# BMS_Adapter_Segment.net
KiCad netlist of a schematic drawn in EAGLE
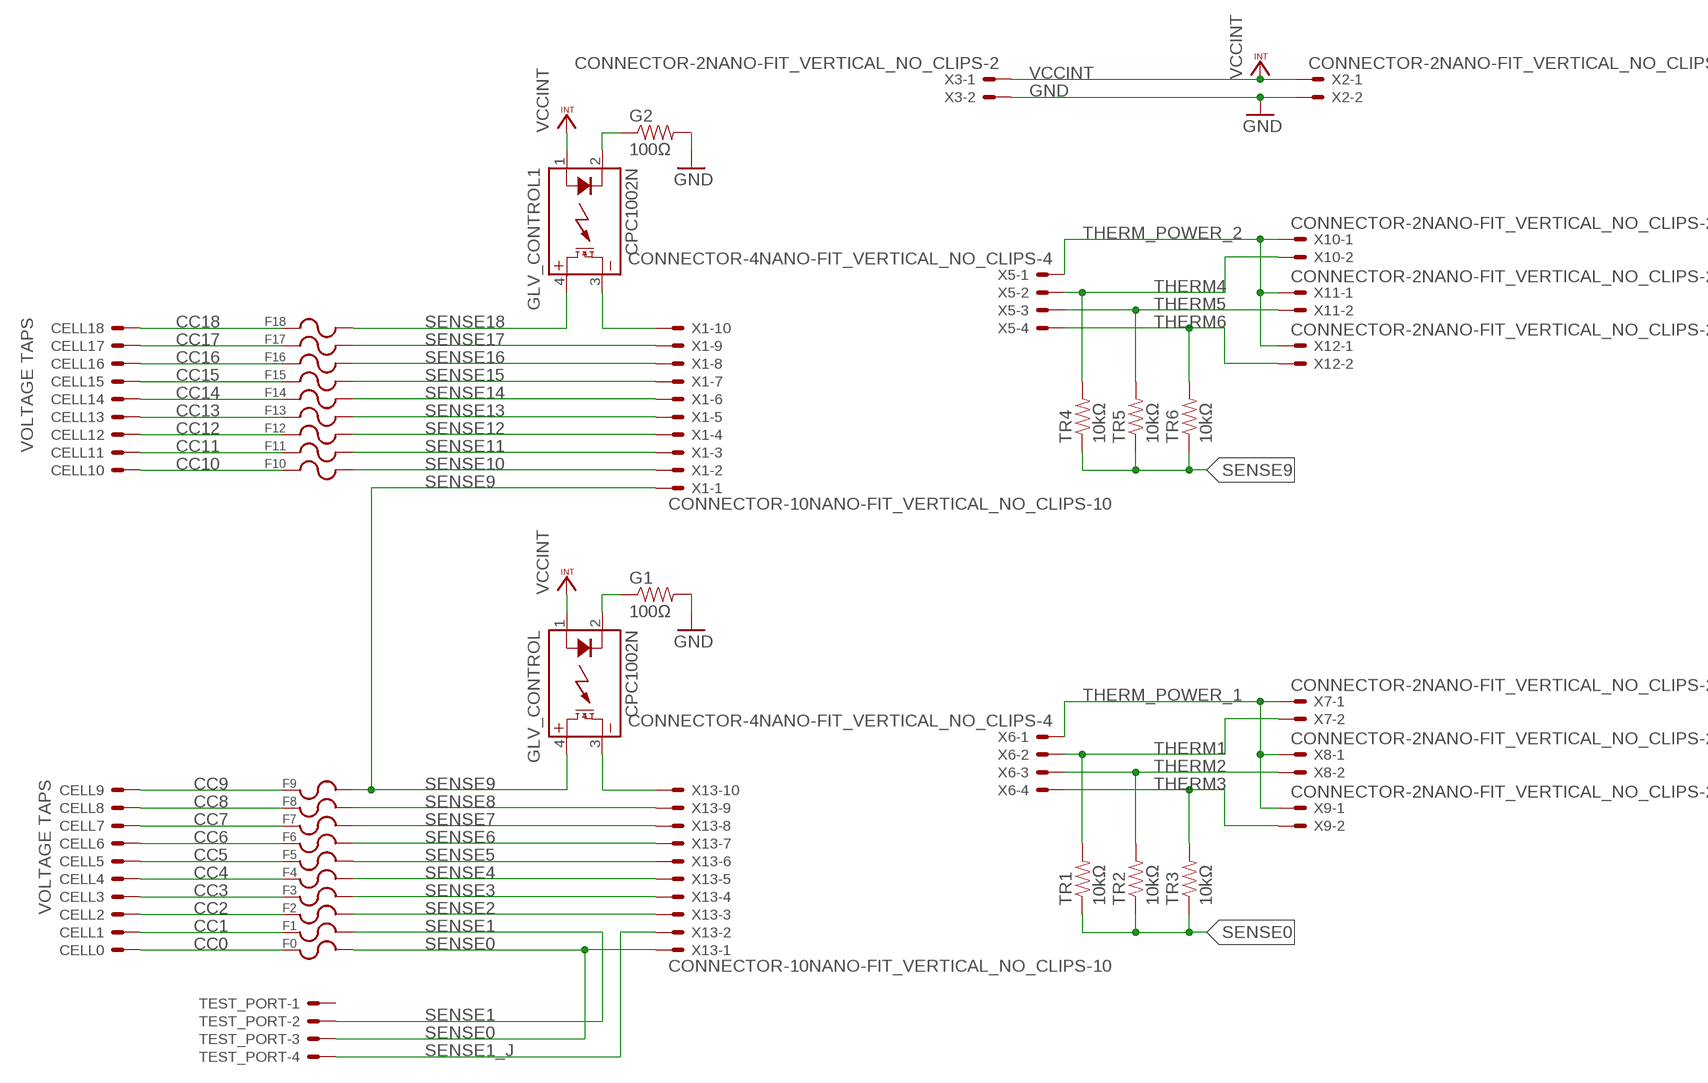
[diagram p0: schematic, sheet 1]

(export (version "E")
  (design (tool "Eeschema 10.0.6"))
  (components
    (comp (ref "CELL0")
      (value "BATTERY_SPRING_KEYSTONE5222")
      (footprint "eagle-import:KEYSTONE5222")
      (libsource (lib "eagle-import") (part "BATTERY_SPRING_KEYSTONE5222"))
    )
    (comp (ref "CELL1")
      (value "BATTERY_SPRING_KEYSTONE5222")
      (footprint "eagle-import:KEYSTONE5222")
      (libsource (lib "eagle-import") (part "BATTERY_SPRING_KEYSTONE5222"))
    )
    (comp (ref "CELL2")
      (value "BATTERY_SPRING_KEYSTONE5222")
      (footprint "eagle-import:KEYSTONE5222")
      (libsource (lib "eagle-import") (part "BATTERY_SPRING_KEYSTONE5222"))
    )
    (comp (ref "CELL3")
      (value "BATTERY_SPRING_KEYSTONE5222")
      (footprint "eagle-import:KEYSTONE5222")
      (libsource (lib "eagle-import") (part "BATTERY_SPRING_KEYSTONE5222"))
    )
    (comp (ref "CELL4")
      (value "BATTERY_SPRING_KEYSTONE5222")
      (footprint "eagle-import:KEYSTONE5222")
      (libsource (lib "eagle-import") (part "BATTERY_SPRING_KEYSTONE5222"))
    )
    (comp (ref "CELL5")
      (value "BATTERY_SPRING_KEYSTONE5222")
      (footprint "eagle-import:KEYSTONE5222")
      (libsource (lib "eagle-import") (part "BATTERY_SPRING_KEYSTONE5222"))
    )
    (comp (ref "CELL6")
      (value "BATTERY_SPRING_KEYSTONE5222")
      (footprint "eagle-import:KEYSTONE5222")
      (libsource (lib "eagle-import") (part "BATTERY_SPRING_KEYSTONE5222"))
    )
    (comp (ref "CELL7")
      (value "BATTERY_SPRING_KEYSTONE5222")
      (footprint "eagle-import:KEYSTONE5222")
      (libsource (lib "eagle-import") (part "BATTERY_SPRING_KEYSTONE5222"))
    )
    (comp (ref "CELL8")
      (value "BATTERY_SPRING_KEYSTONE5222")
      (footprint "eagle-import:KEYSTONE5222")
      (libsource (lib "eagle-import") (part "BATTERY_SPRING_KEYSTONE5222"))
    )
    (comp (ref "CELL9")
      (value "BATTERY_SPRING_KEYSTONE5222")
      (footprint "eagle-import:KEYSTONE5222")
      (libsource (lib "eagle-import") (part "BATTERY_SPRING_KEYSTONE5222"))
    )
    (comp (ref "CELL10")
      (value "BATTERY_SPRING_KEYSTONE5222")
      (footprint "eagle-import:KEYSTONE5222")
      (libsource (lib "eagle-import") (part "BATTERY_SPRING_KEYSTONE5222"))
    )
    (comp (ref "CELL11")
      (value "BATTERY_SPRING_KEYSTONE5222")
      (footprint "eagle-import:KEYSTONE5222")
      (libsource (lib "eagle-import") (part "BATTERY_SPRING_KEYSTONE5222"))
    )
    (comp (ref "CELL12")
      (value "BATTERY_SPRING_KEYSTONE5222")
      (footprint "eagle-import:KEYSTONE5222")
      (libsource (lib "eagle-import") (part "BATTERY_SPRING_KEYSTONE5222"))
    )
    (comp (ref "CELL13")
      (value "BATTERY_SPRING_KEYSTONE5222")
      (footprint "eagle-import:KEYSTONE5222")
      (libsource (lib "eagle-import") (part "BATTERY_SPRING_KEYSTONE5222"))
    )
    (comp (ref "CELL14")
      (value "BATTERY_SPRING_KEYSTONE5222")
      (footprint "eagle-import:KEYSTONE5222")
      (libsource (lib "eagle-import") (part "BATTERY_SPRING_KEYSTONE5222"))
    )
    (comp (ref "CELL15")
      (value "BATTERY_SPRING_KEYSTONE5222")
      (footprint "eagle-import:KEYSTONE5222")
      (libsource (lib "eagle-import") (part "BATTERY_SPRING_KEYSTONE5222"))
    )
    (comp (ref "CELL16")
      (value "BATTERY_SPRING_KEYSTONE5222")
      (footprint "eagle-import:KEYSTONE5222")
      (libsource (lib "eagle-import") (part "BATTERY_SPRING_KEYSTONE5222"))
    )
    (comp (ref "CELL17")
      (value "BATTERY_SPRING_KEYSTONE5222")
      (footprint "eagle-import:KEYSTONE5222")
      (libsource (lib "eagle-import") (part "BATTERY_SPRING_KEYSTONE5222"))
    )
    (comp (ref "CELL18")
      (value "BATTERY_SPRING_KEYSTONE5222")
      (footprint "eagle-import:KEYSTONE5222")
      (libsource (lib "eagle-import") (part "BATTERY_SPRING_KEYSTONE5222"))
    )
    (comp (ref "F0")
      (value "0751.0110_FUSE_CLIP")
      (footprint "eagle-import:0751.0110")
      (libsource (lib "eagle-import") (part "0751.0110_FUSE_CLIP"))
    )
    (comp (ref "F1")
      (value "0751.0110_FUSE_CLIP")
      (footprint "eagle-import:0751.0110")
      (libsource (lib "eagle-import") (part "0751.0110_FUSE_CLIP"))
    )
    (comp (ref "F2")
      (value "0751.0110_FUSE_CLIP")
      (footprint "eagle-import:0751.0110")
      (libsource (lib "eagle-import") (part "0751.0110_FUSE_CLIP"))
    )
    (comp (ref "F3")
      (value "0751.0110_FUSE_CLIP")
      (footprint "eagle-import:0751.0110")
      (libsource (lib "eagle-import") (part "0751.0110_FUSE_CLIP"))
    )
    (comp (ref "F4")
      (value "0751.0110_FUSE_CLIP")
      (footprint "eagle-import:0751.0110")
      (libsource (lib "eagle-import") (part "0751.0110_FUSE_CLIP"))
    )
    (comp (ref "F5")
      (value "0751.0110_FUSE_CLIP")
      (footprint "eagle-import:0751.0110")
      (libsource (lib "eagle-import") (part "0751.0110_FUSE_CLIP"))
    )
    (comp (ref "F6")
      (value "0751.0110_FUSE_CLIP")
      (footprint "eagle-import:0751.0110")
      (libsource (lib "eagle-import") (part "0751.0110_FUSE_CLIP"))
    )
    (comp (ref "F7")
      (value "0751.0110_FUSE_CLIP")
      (footprint "eagle-import:0751.0110")
      (libsource (lib "eagle-import") (part "0751.0110_FUSE_CLIP"))
    )
    (comp (ref "F8")
      (value "0751.0110_FUSE_CLIP")
      (footprint "eagle-import:0751.0110")
      (libsource (lib "eagle-import") (part "0751.0110_FUSE_CLIP"))
    )
    (comp (ref "F9")
      (value "0751.0110_FUSE_CLIP")
      (footprint "eagle-import:0751.0110")
      (libsource (lib "eagle-import") (part "0751.0110_FUSE_CLIP"))
    )
    (comp (ref "F10")
      (value "0751.0110_FUSE_CLIP")
      (footprint "eagle-import:0751.0110")
      (libsource (lib "eagle-import") (part "0751.0110_FUSE_CLIP"))
    )
    (comp (ref "F11")
      (value "0751.0110_FUSE_CLIP")
      (footprint "eagle-import:0751.0110")
      (libsource (lib "eagle-import") (part "0751.0110_FUSE_CLIP"))
    )
    (comp (ref "F12")
      (value "0751.0110_FUSE_CLIP")
      (footprint "eagle-import:0751.0110")
      (libsource (lib "eagle-import") (part "0751.0110_FUSE_CLIP"))
    )
    (comp (ref "F13")
      (value "0751.0110_FUSE_CLIP")
      (footprint "eagle-import:0751.0110")
      (libsource (lib "eagle-import") (part "0751.0110_FUSE_CLIP"))
    )
    (comp (ref "F14")
      (value "0751.0110_FUSE_CLIP")
      (footprint "eagle-import:0751.0110")
      (libsource (lib "eagle-import") (part "0751.0110_FUSE_CLIP"))
    )
    (comp (ref "F15")
      (value "0751.0110_FUSE_CLIP")
      (footprint "eagle-import:0751.0110")
      (libsource (lib "eagle-import") (part "0751.0110_FUSE_CLIP"))
    )
    (comp (ref "F16")
      (value "0751.0110_FUSE_CLIP")
      (footprint "eagle-import:0751.0110")
      (libsource (lib "eagle-import") (part "0751.0110_FUSE_CLIP"))
    )
    (comp (ref "F17")
      (value "0751.0110_FUSE_CLIP")
      (footprint "eagle-import:0751.0110")
      (libsource (lib "eagle-import") (part "0751.0110_FUSE_CLIP"))
    )
    (comp (ref "F18")
      (value "0751.0110_FUSE_CLIP")
      (footprint "eagle-import:0751.0110")
      (libsource (lib "eagle-import") (part "0751.0110_FUSE_CLIP"))
    )
    (comp (ref "G1")
      (value "100Ω")
      (footprint "eagle-import:0805")
      (libsource (lib "eagle-import") (part "RESISTOR0805-RES"))
    )
    (comp (ref "G2")
      (value "100Ω")
      (footprint "eagle-import:0805")
      (libsource (lib "eagle-import") (part "RESISTOR0805-RES"))
    )
    (comp (ref "GLV_CONTROL")
      (value "CPC1002N")
      (footprint "eagle-import:SOP04")
      (libsource (lib "eagle-import") (part "CPC1002N"))
    )
    (comp (ref "GLV_CONTROL1")
      (value "CPC1002N")
      (footprint "eagle-import:SOP04")
      (libsource (lib "eagle-import") (part "CPC1002N"))
    )
    (comp (ref "TEST_PORT")
      (value "MINIFIT_5566-4")
      (footprint "eagle-import:MINIFIT_5566-4")
      (libsource (lib "eagle-import") (part "MINIFIT_5566-4"))
    )
    (comp (ref "TR1")
      (value "10kΩ")
      (footprint "eagle-import:0805")
      (libsource (lib "eagle-import") (part "RESISTOR0805-RES"))
    )
    (comp (ref "TR2")
      (value "10kΩ")
      (footprint "eagle-import:0805")
      (libsource (lib "eagle-import") (part "RESISTOR0805-RES"))
    )
    (comp (ref "TR3")
      (value "10kΩ")
      (footprint "eagle-import:0805")
      (libsource (lib "eagle-import") (part "RESISTOR0805-RES"))
    )
    (comp (ref "TR4")
      (value "10kΩ")
      (footprint "eagle-import:0805")
      (libsource (lib "eagle-import") (part "RESISTOR0805-RES"))
    )
    (comp (ref "TR5")
      (value "10kΩ")
      (footprint "eagle-import:0805")
      (libsource (lib "eagle-import") (part "RESISTOR0805-RES"))
    )
    (comp (ref "TR6")
      (value "10kΩ")
      (footprint "eagle-import:0805")
      (libsource (lib "eagle-import") (part "RESISTOR0805-RES"))
    )
    (comp (ref "X1")
      (value "CONNECTOR-10NANO-FIT_VERTICAL_NO_CLIPS-10")
      (footprint "eagle-import:NANO-FIT_VERTICAL_NO_CLIPS-10")
      (libsource (lib "eagle-import") (part "CONNECTOR-10NANO-FIT_VERTICAL_NO_CLIPS-10"))
    )
    (comp (ref "X2")
      (value "CONNECTOR-2NANO-FIT_VERTICAL_NO_CLIPS-2")
      (footprint "eagle-import:NANO-FIT_VERTICAL_NO_CLIPS-2")
      (libsource (lib "eagle-import") (part "CONNECTOR-2NANO-FIT_VERTICAL_NO_CLIPS-2"))
    )
    (comp (ref "X3")
      (value "CONNECTOR-2NANO-FIT_VERTICAL_NO_CLIPS-2")
      (footprint "eagle-import:NANO-FIT_VERTICAL_NO_CLIPS-2")
      (libsource (lib "eagle-import") (part "CONNECTOR-2NANO-FIT_VERTICAL_NO_CLIPS-2"))
    )
    (comp (ref "X5")
      (value "CONNECTOR-4NANO-FIT_VERTICAL_NO_CLIPS-4")
      (footprint "eagle-import:NANO-FIT_VERTICAL_NO_CLIPS-4")
      (libsource (lib "eagle-import") (part "CONNECTOR-4NANO-FIT_VERTICAL_NO_CLIPS-4"))
    )
    (comp (ref "X6")
      (value "CONNECTOR-4NANO-FIT_VERTICAL_NO_CLIPS-4")
      (footprint "eagle-import:NANO-FIT_VERTICAL_NO_CLIPS-4")
      (libsource (lib "eagle-import") (part "CONNECTOR-4NANO-FIT_VERTICAL_NO_CLIPS-4"))
    )
    (comp (ref "X7")
      (value "CONNECTOR-2NANO-FIT_VERTICAL_NO_CLIPS-2")
      (footprint "eagle-import:NANO-FIT_VERTICAL_NO_CLIPS-2")
      (libsource (lib "eagle-import") (part "CONNECTOR-2NANO-FIT_VERTICAL_NO_CLIPS-2"))
    )
    (comp (ref "X8")
      (value "CONNECTOR-2NANO-FIT_VERTICAL_NO_CLIPS-2")
      (footprint "eagle-import:NANO-FIT_VERTICAL_NO_CLIPS-2")
      (libsource (lib "eagle-import") (part "CONNECTOR-2NANO-FIT_VERTICAL_NO_CLIPS-2"))
    )
    (comp (ref "X9")
      (value "CONNECTOR-2NANO-FIT_VERTICAL_NO_CLIPS-2")
      (footprint "eagle-import:NANO-FIT_VERTICAL_NO_CLIPS-2")
      (libsource (lib "eagle-import") (part "CONNECTOR-2NANO-FIT_VERTICAL_NO_CLIPS-2"))
    )
    (comp (ref "X10")
      (value "CONNECTOR-2NANO-FIT_VERTICAL_NO_CLIPS-2")
      (footprint "eagle-import:NANO-FIT_VERTICAL_NO_CLIPS-2")
      (libsource (lib "eagle-import") (part "CONNECTOR-2NANO-FIT_VERTICAL_NO_CLIPS-2"))
    )
    (comp (ref "X11")
      (value "CONNECTOR-2NANO-FIT_VERTICAL_NO_CLIPS-2")
      (footprint "eagle-import:NANO-FIT_VERTICAL_NO_CLIPS-2")
      (libsource (lib "eagle-import") (part "CONNECTOR-2NANO-FIT_VERTICAL_NO_CLIPS-2"))
    )
    (comp (ref "X12")
      (value "CONNECTOR-2NANO-FIT_VERTICAL_NO_CLIPS-2")
      (footprint "eagle-import:NANO-FIT_VERTICAL_NO_CLIPS-2")
      (libsource (lib "eagle-import") (part "CONNECTOR-2NANO-FIT_VERTICAL_NO_CLIPS-2"))
    )
    (comp (ref "X13")
      (value "CONNECTOR-10NANO-FIT_VERTICAL_NO_CLIPS-10")
      (footprint "eagle-import:NANO-FIT_VERTICAL_NO_CLIPS-10")
      (libsource (lib "eagle-import") (part "CONNECTOR-10NANO-FIT_VERTICAL_NO_CLIPS-10"))
    )
  )
  (nets
    (net (code "1") (name "/CC0") (class "Default")
      (node (ref "CELL0") (pin "P$1") (pinfunction "S_P$1") (pintype "passive"))
      (node (ref "F0") (pin "L1") (pinfunction "1_L1") (pintype "bidirectional"))
      (node (ref "F0") (pin "L2") (pinfunction "1_L2") (pintype "bidirectional"))
    )
    (net (code "2") (name "/CC1") (class "Default")
      (node (ref "CELL1") (pin "P$1") (pinfunction "S_P$1") (pintype "passive"))
      (node (ref "F1") (pin "L1") (pinfunction "1_L1") (pintype "bidirectional"))
      (node (ref "F1") (pin "L2") (pinfunction "1_L2") (pintype "bidirectional"))
    )
    (net (code "3") (name "/CC2") (class "Default")
      (node (ref "CELL2") (pin "P$1") (pinfunction "S_P$1") (pintype "passive"))
      (node (ref "F2") (pin "L1") (pinfunction "1_L1") (pintype "bidirectional"))
      (node (ref "F2") (pin "L2") (pinfunction "1_L2") (pintype "bidirectional"))
    )
    (net (code "4") (name "/CC3") (class "Default")
      (node (ref "CELL3") (pin "P$1") (pinfunction "S_P$1") (pintype "passive"))
      (node (ref "F3") (pin "L1") (pinfunction "1_L1") (pintype "bidirectional"))
      (node (ref "F3") (pin "L2") (pinfunction "1_L2") (pintype "bidirectional"))
    )
    (net (code "5") (name "/CC4") (class "Default")
      (node (ref "CELL4") (pin "P$1") (pinfunction "S_P$1") (pintype "passive"))
      (node (ref "F4") (pin "L1") (pinfunction "1_L1") (pintype "bidirectional"))
      (node (ref "F4") (pin "L2") (pinfunction "1_L2") (pintype "bidirectional"))
    )
    (net (code "6") (name "/CC5") (class "Default")
      (node (ref "CELL5") (pin "P$1") (pinfunction "S_P$1") (pintype "passive"))
      (node (ref "F5") (pin "L1") (pinfunction "1_L1") (pintype "bidirectional"))
      (node (ref "F5") (pin "L2") (pinfunction "1_L2") (pintype "bidirectional"))
    )
    (net (code "7") (name "/CC6") (class "Default")
      (node (ref "CELL6") (pin "P$1") (pinfunction "S_P$1") (pintype "passive"))
      (node (ref "F6") (pin "L1") (pinfunction "1_L1") (pintype "bidirectional"))
      (node (ref "F6") (pin "L2") (pinfunction "1_L2") (pintype "bidirectional"))
    )
    (net (code "8") (name "/CC7") (class "Default")
      (node (ref "CELL7") (pin "P$1") (pinfunction "S_P$1") (pintype "passive"))
      (node (ref "F7") (pin "L1") (pinfunction "1_L1") (pintype "bidirectional"))
      (node (ref "F7") (pin "L2") (pinfunction "1_L2") (pintype "bidirectional"))
    )
    (net (code "9") (name "/CC8") (class "Default")
      (node (ref "CELL8") (pin "P$1") (pinfunction "S_P$1") (pintype "passive"))
      (node (ref "F8") (pin "L1") (pinfunction "1_L1") (pintype "bidirectional"))
      (node (ref "F8") (pin "L2") (pinfunction "1_L2") (pintype "bidirectional"))
    )
    (net (code "10") (name "/CC9") (class "Default")
      (node (ref "CELL9") (pin "P$1") (pinfunction "S_P$1") (pintype "passive"))
      (node (ref "F9") (pin "L1") (pinfunction "1_L1") (pintype "bidirectional"))
      (node (ref "F9") (pin "L2") (pinfunction "1_L2") (pintype "bidirectional"))
    )
    (net (code "11") (name "/CC10") (class "Default")
      (node (ref "CELL10") (pin "P$1") (pinfunction "S_P$1") (pintype "passive"))
      (node (ref "F10") (pin "L1") (pinfunction "1_L1") (pintype "bidirectional"))
      (node (ref "F10") (pin "L2") (pinfunction "1_L2") (pintype "bidirectional"))
    )
    (net (code "12") (name "/CC11") (class "Default")
      (node (ref "CELL11") (pin "P$1") (pinfunction "S_P$1") (pintype "passive"))
      (node (ref "F11") (pin "L1") (pinfunction "1_L1") (pintype "bidirectional"))
      (node (ref "F11") (pin "L2") (pinfunction "1_L2") (pintype "bidirectional"))
    )
    (net (code "13") (name "/CC12") (class "Default")
      (node (ref "CELL12") (pin "P$1") (pinfunction "S_P$1") (pintype "passive"))
      (node (ref "F12") (pin "L1") (pinfunction "1_L1") (pintype "bidirectional"))
      (node (ref "F12") (pin "L2") (pinfunction "1_L2") (pintype "bidirectional"))
    )
    (net (code "14") (name "/CC13") (class "Default")
      (node (ref "CELL13") (pin "P$1") (pinfunction "S_P$1") (pintype "passive"))
      (node (ref "F13") (pin "L1") (pinfunction "1_L1") (pintype "bidirectional"))
      (node (ref "F13") (pin "L2") (pinfunction "1_L2") (pintype "bidirectional"))
    )
    (net (code "15") (name "/CC14") (class "Default")
      (node (ref "CELL14") (pin "P$1") (pinfunction "S_P$1") (pintype "passive"))
      (node (ref "F14") (pin "L1") (pinfunction "1_L1") (pintype "bidirectional"))
      (node (ref "F14") (pin "L2") (pinfunction "1_L2") (pintype "bidirectional"))
    )
    (net (code "16") (name "/CC15") (class "Default")
      (node (ref "CELL15") (pin "P$1") (pinfunction "S_P$1") (pintype "passive"))
      (node (ref "F15") (pin "L1") (pinfunction "1_L1") (pintype "bidirectional"))
      (node (ref "F15") (pin "L2") (pinfunction "1_L2") (pintype "bidirectional"))
    )
    (net (code "17") (name "/CC16") (class "Default")
      (node (ref "CELL16") (pin "P$1") (pinfunction "S_P$1") (pintype "passive"))
      (node (ref "F16") (pin "L1") (pinfunction "1_L1") (pintype "bidirectional"))
      (node (ref "F16") (pin "L2") (pinfunction "1_L2") (pintype "bidirectional"))
    )
    (net (code "18") (name "/CC17") (class "Default")
      (node (ref "CELL17") (pin "P$1") (pinfunction "S_P$1") (pintype "passive"))
      (node (ref "F17") (pin "L1") (pinfunction "1_L1") (pintype "bidirectional"))
      (node (ref "F17") (pin "L2") (pinfunction "1_L2") (pintype "bidirectional"))
    )
    (net (code "19") (name "/CC18") (class "Default")
      (node (ref "CELL18") (pin "P$1") (pinfunction "S_P$1") (pintype "passive"))
      (node (ref "F18") (pin "L1") (pinfunction "1_L1") (pintype "bidirectional"))
      (node (ref "F18") (pin "L2") (pinfunction "1_L2") (pintype "bidirectional"))
    )
    (net (code "20") (name "/SENSE1") (class "Default")
      (node (ref "F1") (pin "R1") (pinfunction "2_R1") (pintype "bidirectional"))
      (node (ref "F1") (pin "R2") (pinfunction "2_R2") (pintype "bidirectional"))
      (node (ref "TEST_PORT") (pin "2") (pinfunction "S_2") (pintype "passive"))
    )
    (net (code "21") (name "/SENSE1_J") (class "Default")
      (node (ref "TEST_PORT") (pin "4") (pinfunction "S_4") (pintype "passive"))
      (node (ref "X13") (pin "P$2") (pinfunction "S_P$2") (pintype "passive"))
    )
    (net (code "22") (name "/SENSE2") (class "Default")
      (node (ref "F2") (pin "R1") (pinfunction "2_R1") (pintype "bidirectional"))
      (node (ref "F2") (pin "R2") (pinfunction "2_R2") (pintype "bidirectional"))
      (node (ref "X13") (pin "P$3") (pinfunction "S_P$3") (pintype "passive"))
    )
    (net (code "23") (name "/SENSE3") (class "Default")
      (node (ref "F3") (pin "R1") (pinfunction "2_R1") (pintype "bidirectional"))
      (node (ref "F3") (pin "R2") (pinfunction "2_R2") (pintype "bidirectional"))
      (node (ref "X13") (pin "P$4") (pinfunction "S_P$4") (pintype "passive"))
    )
    (net (code "24") (name "/SENSE4") (class "Default")
      (node (ref "F4") (pin "R1") (pinfunction "2_R1") (pintype "bidirectional"))
      (node (ref "F4") (pin "R2") (pinfunction "2_R2") (pintype "bidirectional"))
      (node (ref "X13") (pin "P$5") (pinfunction "S_P$5") (pintype "passive"))
    )
    (net (code "25") (name "/SENSE5") (class "Default")
      (node (ref "F5") (pin "R1") (pinfunction "2_R1") (pintype "bidirectional"))
      (node (ref "F5") (pin "R2") (pinfunction "2_R2") (pintype "bidirectional"))
      (node (ref "X13") (pin "P$6") (pinfunction "S_P$6") (pintype "passive"))
    )
    (net (code "26") (name "/SENSE6") (class "Default")
      (node (ref "F6") (pin "R1") (pinfunction "2_R1") (pintype "bidirectional"))
      (node (ref "F6") (pin "R2") (pinfunction "2_R2") (pintype "bidirectional"))
      (node (ref "X13") (pin "P$7") (pinfunction "S_P$7") (pintype "passive"))
    )
    (net (code "27") (name "/SENSE7") (class "Default")
      (node (ref "F7") (pin "R1") (pinfunction "2_R1") (pintype "bidirectional"))
      (node (ref "F7") (pin "R2") (pinfunction "2_R2") (pintype "bidirectional"))
      (node (ref "X13") (pin "P$8") (pinfunction "S_P$8") (pintype "passive"))
    )
    (net (code "28") (name "/SENSE8") (class "Default")
      (node (ref "F8") (pin "R1") (pinfunction "2_R1") (pintype "bidirectional"))
      (node (ref "F8") (pin "R2") (pinfunction "2_R2") (pintype "bidirectional"))
      (node (ref "X13") (pin "P$9") (pinfunction "S_P$9") (pintype "passive"))
    )
    (net (code "29") (name "/SENSE10") (class "Default")
      (node (ref "F10") (pin "R1") (pinfunction "2_R1") (pintype "bidirectional"))
      (node (ref "F10") (pin "R2") (pinfunction "2_R2") (pintype "bidirectional"))
      (node (ref "X1") (pin "P$2") (pinfunction "S_P$2") (pintype "passive"))
    )
    (net (code "30") (name "/SENSE11") (class "Default")
      (node (ref "F11") (pin "R1") (pinfunction "2_R1") (pintype "bidirectional"))
      (node (ref "F11") (pin "R2") (pinfunction "2_R2") (pintype "bidirectional"))
      (node (ref "X1") (pin "P$3") (pinfunction "S_P$3") (pintype "passive"))
    )
    (net (code "31") (name "/SENSE12") (class "Default")
      (node (ref "F12") (pin "R1") (pinfunction "2_R1") (pintype "bidirectional"))
      (node (ref "F12") (pin "R2") (pinfunction "2_R2") (pintype "bidirectional"))
      (node (ref "X1") (pin "P$4") (pinfunction "S_P$4") (pintype "passive"))
    )
    (net (code "32") (name "/SENSE13") (class "Default")
      (node (ref "F13") (pin "R1") (pinfunction "2_R1") (pintype "bidirectional"))
      (node (ref "F13") (pin "R2") (pinfunction "2_R2") (pintype "bidirectional"))
      (node (ref "X1") (pin "P$5") (pinfunction "S_P$5") (pintype "passive"))
    )
    (net (code "33") (name "/SENSE14") (class "Default")
      (node (ref "F14") (pin "R1") (pinfunction "2_R1") (pintype "bidirectional"))
      (node (ref "F14") (pin "R2") (pinfunction "2_R2") (pintype "bidirectional"))
      (node (ref "X1") (pin "P$6") (pinfunction "S_P$6") (pintype "passive"))
    )
    (net (code "34") (name "/SENSE15") (class "Default")
      (node (ref "F15") (pin "R1") (pinfunction "2_R1") (pintype "bidirectional"))
      (node (ref "F15") (pin "R2") (pinfunction "2_R2") (pintype "bidirectional"))
      (node (ref "X1") (pin "P$7") (pinfunction "S_P$7") (pintype "passive"))
    )
    (net (code "35") (name "/SENSE16") (class "Default")
      (node (ref "F16") (pin "R1") (pinfunction "2_R1") (pintype "bidirectional"))
      (node (ref "F16") (pin "R2") (pinfunction "2_R2") (pintype "bidirectional"))
      (node (ref "X1") (pin "P$8") (pinfunction "S_P$8") (pintype "passive"))
    )
    (net (code "36") (name "/SENSE17") (class "Default")
      (node (ref "F17") (pin "R1") (pinfunction "2_R1") (pintype "bidirectional"))
      (node (ref "F17") (pin "R2") (pinfunction "2_R2") (pintype "bidirectional"))
      (node (ref "X1") (pin "P$9") (pinfunction "S_P$9") (pintype "passive"))
    )
    (net (code "37") (name "/SENSE18") (class "Default")
      (node (ref "F18") (pin "R1") (pinfunction "2_R1") (pintype "bidirectional"))
      (node (ref "F18") (pin "R2") (pinfunction "2_R2") (pintype "bidirectional"))
      (node (ref "GLV_CONTROL1") (pin "4") (pinfunction "DC+_4") (pintype "passive"))
    )
    (net (code "38") (name "/THERM1") (class "Default")
      (node (ref "TR1") (pin "2") (pinfunction "2_2") (pintype "passive"))
      (node (ref "X6") (pin "P$2") (pinfunction "S_P$2") (pintype "passive"))
      (node (ref "X7") (pin "P$2") (pinfunction "S_P$2") (pintype "passive"))
    )
    (net (code "39") (name "/THERM2") (class "Default")
      (node (ref "TR2") (pin "2") (pinfunction "2_2") (pintype "passive"))
      (node (ref "X6") (pin "P$3") (pinfunction "S_P$3") (pintype "passive"))
      (node (ref "X8") (pin "P$2") (pinfunction "S_P$2") (pintype "passive"))
    )
    (net (code "40") (name "/THERM3") (class "Default")
      (node (ref "TR3") (pin "2") (pinfunction "2_2") (pintype "passive"))
      (node (ref "X6") (pin "P$4") (pinfunction "S_P$4") (pintype "passive"))
      (node (ref "X9") (pin "P$2") (pinfunction "S_P$2") (pintype "passive"))
    )
    (net (code "41") (name "/THERM4") (class "Default")
      (node (ref "TR4") (pin "2") (pinfunction "2_2") (pintype "passive"))
      (node (ref "X10") (pin "P$2") (pinfunction "S_P$2") (pintype "passive"))
      (node (ref "X5") (pin "P$2") (pinfunction "S_P$2") (pintype "passive"))
    )
    (net (code "42") (name "/THERM5") (class "Default")
      (node (ref "TR5") (pin "2") (pinfunction "2_2") (pintype "passive"))
      (node (ref "X11") (pin "P$2") (pinfunction "S_P$2") (pintype "passive"))
      (node (ref "X5") (pin "P$3") (pinfunction "S_P$3") (pintype "passive"))
    )
    (net (code "43") (name "/THERM6") (class "Default")
      (node (ref "TR6") (pin "2") (pinfunction "2_2") (pintype "passive"))
      (node (ref "X12") (pin "P$2") (pinfunction "S_P$2") (pintype "passive"))
      (node (ref "X5") (pin "P$4") (pinfunction "S_P$4") (pintype "passive"))
    )
    (net (code "44") (name "/THERM_POWER_1") (class "Default")
      (node (ref "X6") (pin "P$1") (pinfunction "S_P$1") (pintype "passive"))
      (node (ref "X7") (pin "P$1") (pinfunction "S_P$1") (pintype "passive"))
      (node (ref "X8") (pin "P$1") (pinfunction "S_P$1") (pintype "passive"))
      (node (ref "X9") (pin "P$1") (pinfunction "S_P$1") (pintype "passive"))
    )
    (net (code "45") (name "/THERM_POWER_2") (class "Default")
      (node (ref "X10") (pin "P$1") (pinfunction "S_P$1") (pintype "passive"))
      (node (ref "X11") (pin "P$1") (pinfunction "S_P$1") (pintype "passive"))
      (node (ref "X12") (pin "P$1") (pinfunction "S_P$1") (pintype "passive"))
      (node (ref "X5") (pin "P$1") (pinfunction "S_P$1") (pintype "passive"))
    )
    (net (code "46") (name "GND") (class "Default")
      (node (ref "G1") (pin "2") (pinfunction "2_2") (pintype "passive"))
      (node (ref "G2") (pin "2") (pinfunction "2_2") (pintype "passive"))
      (node (ref "X2") (pin "P$2") (pinfunction "S_P$2") (pintype "passive"))
      (node (ref "X3") (pin "P$2") (pinfunction "S_P$2") (pintype "passive"))
    )
    (net (code "47") (name "Net-(GLV_CONTROL-CONTROL-)") (class "Default")
      (node (ref "G1") (pin "1") (pinfunction "1_1") (pintype "passive"))
      (node (ref "GLV_CONTROL") (pin "2") (pinfunction "CONTROL-_2") (pintype "passive"))
    )
    (net (code "48") (name "Net-(GLV_CONTROL-DC-)") (class "Default")
      (node (ref "GLV_CONTROL") (pin "3") (pinfunction "DC-_3") (pintype "passive"))
      (node (ref "X13") (pin "P$10") (pinfunction "S_P$10") (pintype "passive"))
    )
    (net (code "49") (name "Net-(GLV_CONTROL1-CONTROL-)") (class "Default")
      (node (ref "G2") (pin "1") (pinfunction "1_1") (pintype "passive"))
      (node (ref "GLV_CONTROL1") (pin "2") (pinfunction "CONTROL-_2") (pintype "passive"))
    )
    (net (code "50") (name "Net-(GLV_CONTROL1-DC-)") (class "Default")
      (node (ref "GLV_CONTROL1") (pin "3") (pinfunction "DC-_3") (pintype "passive"))
      (node (ref "X1") (pin "P$10") (pinfunction "S_P$10") (pintype "passive"))
    )
    (net (code "51") (name "SENSE0") (class "Default")
      (node (ref "F0") (pin "R1") (pinfunction "2_R1") (pintype "bidirectional"))
      (node (ref "F0") (pin "R2") (pinfunction "2_R2") (pintype "bidirectional"))
      (node (ref "TEST_PORT") (pin "3") (pinfunction "S_3") (pintype "passive"))
      (node (ref "TR1") (pin "1") (pinfunction "1_1") (pintype "passive"))
      (node (ref "TR2") (pin "1") (pinfunction "1_1") (pintype "passive"))
      (node (ref "TR3") (pin "1") (pinfunction "1_1") (pintype "passive"))
      (node (ref "X13") (pin "P$1") (pinfunction "S_P$1") (pintype "passive"))
    )
    (net (code "52") (name "SENSE9") (class "Default")
      (node (ref "F9") (pin "R1") (pinfunction "2_R1") (pintype "bidirectional"))
      (node (ref "F9") (pin "R2") (pinfunction "2_R2") (pintype "bidirectional"))
      (node (ref "GLV_CONTROL") (pin "4") (pinfunction "DC+_4") (pintype "passive"))
      (node (ref "TR4") (pin "1") (pinfunction "1_1") (pintype "passive"))
      (node (ref "TR5") (pin "1") (pinfunction "1_1") (pintype "passive"))
      (node (ref "TR6") (pin "1") (pinfunction "1_1") (pintype "passive"))
      (node (ref "X1") (pin "P$1") (pinfunction "S_P$1") (pintype "passive"))
    )
    (net (code "53") (name "VCCINT") (class "Default")
      (node (ref "GLV_CONTROL") (pin "1") (pinfunction "CONTROL+_1") (pintype "passive"))
      (node (ref "GLV_CONTROL1") (pin "1") (pinfunction "CONTROL+_1") (pintype "passive"))
      (node (ref "X2") (pin "P$1") (pinfunction "S_P$1") (pintype "passive"))
      (node (ref "X3") (pin "P$1") (pinfunction "S_P$1") (pintype "passive"))
    )
    (net (code "54") (name "unconnected-(TEST_PORTA-S-Pad1)") (class "Default")
      (node (ref "TEST_PORT") (pin "1") (pinfunction "S_1") (pintype "passive"))
    )
  )
)
